# solar_collector_controller_V1_21.net
KiCad netlist of a schematic drawn in EAGLE
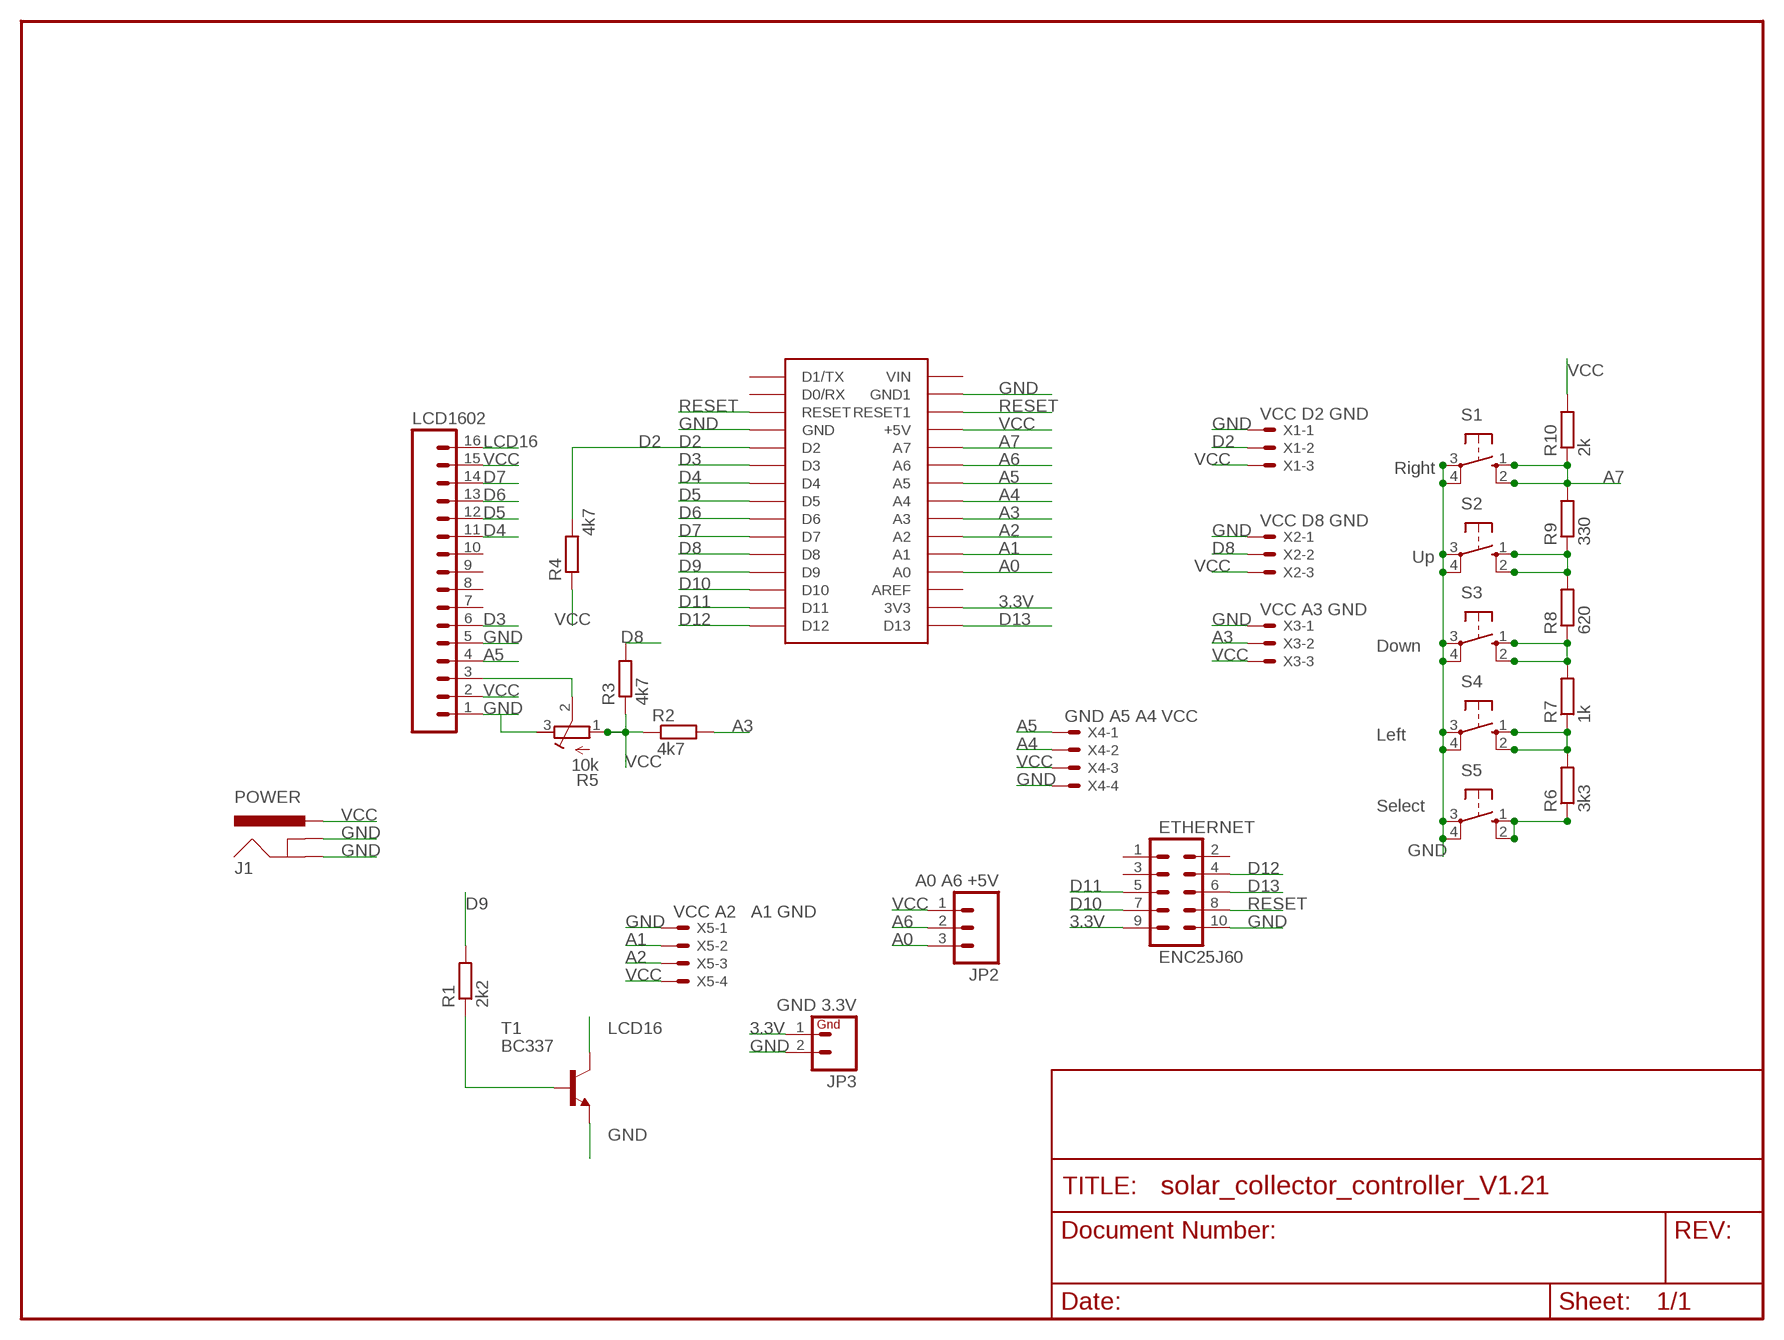
[diagram p0: schematic, sheet 1]

(export (version "E")
  (design (tool "Eeschema 10.0.6"))
  (components
    (comp (ref "ETHERNET")
      (value "ENC25J60")
      (footprint "eagle-import:AVR_ICSP")
      (libsource (lib "eagle-import") (part "M05X2PTH"))
    )
    (comp (ref "J1")
      (value "POWER")
      (footprint "eagle-import:POWER_JACK_PTH_LOCK")
      (libsource (lib "eagle-import") (part "POWER_JACKPTH_LOCK"))
    )
    (comp (ref "JP2")
      (value "A0 A6 +5V")
      (footprint "eagle-import:1X03")
      (libsource (lib "eagle-import") (part "M03PTH"))
    )
    (comp (ref "JP3")
      (value "GND 3.3V")
      (footprint "eagle-import:1X02")
      (libsource (lib "eagle-import") (part "M02PTH"))
    )
    (comp (ref "LCD1602")
      (value "HEADER-16P-2.54")
      (footprint "eagle-import:16P-2.54")
      (libsource (lib "eagle-import") (part "HEADER-16P-2.54"))
    )
    (comp (ref "R1")
      (value "2k2")
      (footprint "eagle-import:0207_10")
      (libsource (lib "eagle-import") (part "R-EU_0207/10"))
    )
    (comp (ref "R2")
      (value "4k7")
      (footprint "eagle-import:0207_10")
      (libsource (lib "eagle-import") (part "R-EU_0207/10"))
    )
    (comp (ref "R3")
      (value "4k7")
      (footprint "eagle-import:0207_10")
      (libsource (lib "eagle-import") (part "R-EU_0207/10"))
    )
    (comp (ref "R4")
      (value "4k7")
      (footprint "eagle-import:0207_10")
      (libsource (lib "eagle-import") (part "R-EU_0207/10"))
    )
    (comp (ref "R5")
      (value "10k")
      (footprint "eagle-import:RTRIM64W")
      (libsource (lib "eagle-import") (part "R-TRIMM64W"))
    )
    (comp (ref "R6")
      (value "3k3")
      (footprint "eagle-import:0207_10")
      (libsource (lib "eagle-import") (part "R-EU_0207/10"))
    )
    (comp (ref "R7")
      (value "1k")
      (footprint "eagle-import:0207_10")
      (libsource (lib "eagle-import") (part "R-EU_0207/10"))
    )
    (comp (ref "R8")
      (value "620")
      (footprint "eagle-import:0207_10")
      (libsource (lib "eagle-import") (part "R-EU_0207/10"))
    )
    (comp (ref "R9")
      (value "330")
      (footprint "eagle-import:0207_10")
      (libsource (lib "eagle-import") (part "R-EU_0207/10"))
    )
    (comp (ref "R10")
      (value "2k")
      (footprint "eagle-import:0207_10")
      (libsource (lib "eagle-import") (part "R-EU_0207/10"))
    )
    (comp (ref "S1")
      (value "Right")
      (footprint "eagle-import:B3F-10XX")
      (fields (field (name "MPN") "B3F-1000"))
      (libsource (lib "eagle-import") (part "10-XX"))
    )
    (comp (ref "S2")
      (value "Up")
      (footprint "eagle-import:B3F-10XX")
      (fields (field (name "MPN") "B3F-1000"))
      (libsource (lib "eagle-import") (part "10-XX"))
    )
    (comp (ref "S3")
      (value "Down")
      (footprint "eagle-import:B3F-10XX")
      (fields (field (name "MPN") "B3F-1000"))
      (libsource (lib "eagle-import") (part "10-XX"))
    )
    (comp (ref "S4")
      (value "Left")
      (footprint "eagle-import:B3F-10XX")
      (fields (field (name "MPN") "B3F-1000"))
      (libsource (lib "eagle-import") (part "10-XX"))
    )
    (comp (ref "S5")
      (value "Select")
      (footprint "eagle-import:B3F-10XX")
      (fields (field (name "MPN") "B3F-1000"))
      (libsource (lib "eagle-import") (part "10-XX"))
    )
    (comp (ref "T1")
      (value "BC337")
      (footprint "eagle-import:TO92")
      (libsource (lib "eagle-import") (part "BC337"))
    )
    (comp (ref "U$2")
      (value "ARDUINONANO")
      (footprint "eagle-import:PDIP-32")
      (libsource (lib "eagle-import") (part "ARDUINONANO"))
    )
    (comp (ref "X1")
      (value "VCC D2 GND")
      (footprint "eagle-import:22-23-2031")
      (fields (field (name "MF") "MOLEX") (field (name "MPN") "22-23-2031"))
      (libsource (lib "eagle-import") (part "22-23-2031"))
    )
    (comp (ref "X2")
      (value "VCC D8 GND")
      (footprint "eagle-import:22-23-2031")
      (fields (field (name "MF") "MOLEX") (field (name "MPN") "22-23-2031"))
      (libsource (lib "eagle-import") (part "22-23-2031"))
    )
    (comp (ref "X3")
      (value "VCC A3 GND")
      (footprint "eagle-import:22-23-2031")
      (fields (field (name "MF") "MOLEX") (field (name "MPN") "22-23-2031"))
      (libsource (lib "eagle-import") (part "22-23-2031"))
    )
    (comp (ref "X4")
      (value "GND A5 A4 VCC")
      (footprint "eagle-import:22-23-2041")
      (fields (field (name "MF") "MOLEX") (field (name "MPN") "22-23-2041"))
      (libsource (lib "eagle-import") (part "22-23-2041"))
    )
    (comp (ref "X5")
      (value "VCC A2 A1 GND")
      (footprint "eagle-import:22-23-2041")
      (fields (field (name "MF") "MOLEX") (field (name "MPN") "22-23-2041"))
      (libsource (lib "eagle-import") (part "22-23-2041"))
    )
  )
  (nets
    (net (code "1") (name "/3.3V") (class "Default")
      (node (ref "ETHERNET") (pin "9") (pinfunction "9_9") (pintype "passive"))
      (node (ref "JP3") (pin "1") (pinfunction "1_1") (pintype "passive"))
      (node (ref "U$2") (pin "3V3") (pinfunction "3V3_3V3") (pintype "bidirectional"))
    )
    (net (code "2") (name "/A0") (class "Default")
      (node (ref "JP2") (pin "3") (pinfunction "3_3") (pintype "passive"))
      (node (ref "U$2") (pin "A0") (pinfunction "A0_A0") (pintype "bidirectional"))
    )
    (net (code "3") (name "/A1") (class "Default")
      (node (ref "U$2") (pin "A1") (pinfunction "A1_A1") (pintype "bidirectional"))
      (node (ref "X5") (pin "2") (pinfunction "S_2") (pintype "passive"))
    )
    (net (code "4") (name "/A2") (class "Default")
      (node (ref "U$2") (pin "A2") (pinfunction "A2_A2") (pintype "bidirectional"))
      (node (ref "X5") (pin "3") (pinfunction "S_3") (pintype "passive"))
    )
    (net (code "5") (name "/A3") (class "Default")
      (node (ref "R2") (pin "2") (pinfunction "2_2") (pintype "passive"))
      (node (ref "U$2") (pin "A3") (pinfunction "A3_A3") (pintype "bidirectional"))
      (node (ref "X3") (pin "2") (pinfunction "S_2") (pintype "passive"))
    )
    (net (code "6") (name "/A4") (class "Default")
      (node (ref "U$2") (pin "A4") (pinfunction "A4_A4") (pintype "bidirectional"))
      (node (ref "X4") (pin "2") (pinfunction "S_2") (pintype "passive"))
    )
    (net (code "7") (name "/A5") (class "Default")
      (node (ref "LCD1602") (pin "4") (pinfunction "4_4") (pintype "passive"))
      (node (ref "U$2") (pin "A5") (pinfunction "A5_A5") (pintype "bidirectional"))
      (node (ref "X4") (pin "1") (pinfunction "S_1") (pintype "passive"))
    )
    (net (code "8") (name "/A6") (class "Default")
      (node (ref "JP2") (pin "2") (pinfunction "2_2") (pintype "passive"))
      (node (ref "U$2") (pin "A6") (pinfunction "A6_A6") (pintype "bidirectional"))
    )
    (net (code "9") (name "/A7") (class "Default")
      (node (ref "R10") (pin "1") (pinfunction "1_1") (pintype "passive"))
      (node (ref "R9") (pin "2") (pinfunction "2_2") (pintype "passive"))
      (node (ref "S1") (pin "1") (pinfunction "S_1") (pintype "passive"))
      (node (ref "S1") (pin "2") (pinfunction "S1_2") (pintype "passive"))
      (node (ref "U$2") (pin "A7") (pinfunction "A7_A7") (pintype "bidirectional"))
    )
    (net (code "10") (name "/D2") (class "Default")
      (node (ref "R4") (pin "2") (pinfunction "2_2") (pintype "passive"))
      (node (ref "U$2") (pin "D2") (pinfunction "D2_D2") (pintype "bidirectional"))
      (node (ref "X1") (pin "2") (pinfunction "S_2") (pintype "passive"))
    )
    (net (code "11") (name "/D3") (class "Default")
      (node (ref "LCD1602") (pin "6") (pinfunction "6_6") (pintype "passive"))
      (node (ref "U$2") (pin "D3") (pinfunction "D3_D3") (pintype "bidirectional"))
    )
    (net (code "12") (name "/D4") (class "Default")
      (node (ref "LCD1602") (pin "11") (pinfunction "11_11") (pintype "passive"))
      (node (ref "U$2") (pin "D4") (pinfunction "D4_D4") (pintype "bidirectional"))
    )
    (net (code "13") (name "/D5") (class "Default")
      (node (ref "LCD1602") (pin "12") (pinfunction "12_12") (pintype "passive"))
      (node (ref "U$2") (pin "D5") (pinfunction "D5_D5") (pintype "bidirectional"))
    )
    (net (code "14") (name "/D6") (class "Default")
      (node (ref "LCD1602") (pin "13") (pinfunction "13_13") (pintype "passive"))
      (node (ref "U$2") (pin "D6") (pinfunction "D6_D6") (pintype "bidirectional"))
    )
    (net (code "15") (name "/D7") (class "Default")
      (node (ref "LCD1602") (pin "14") (pinfunction "14_14") (pintype "passive"))
      (node (ref "U$2") (pin "D7") (pinfunction "D7_D7") (pintype "bidirectional"))
    )
    (net (code "16") (name "/D8") (class "Default")
      (node (ref "R3") (pin "2") (pinfunction "2_2") (pintype "passive"))
      (node (ref "U$2") (pin "D8") (pinfunction "D8_D8") (pintype "bidirectional"))
      (node (ref "X2") (pin "2") (pinfunction "S_2") (pintype "passive"))
    )
    (net (code "17") (name "/D9") (class "Default")
      (node (ref "R1") (pin "2") (pinfunction "2_2") (pintype "passive"))
      (node (ref "U$2") (pin "D9") (pinfunction "D9_D9") (pintype "bidirectional"))
    )
    (net (code "18") (name "/D10") (class "Default")
      (node (ref "ETHERNET") (pin "7") (pinfunction "7_7") (pintype "passive"))
      (node (ref "U$2") (pin "D10") (pinfunction "D10_D10") (pintype "bidirectional"))
    )
    (net (code "19") (name "/D11") (class "Default")
      (node (ref "ETHERNET") (pin "5") (pinfunction "5_5") (pintype "passive"))
      (node (ref "U$2") (pin "D11") (pinfunction "D11_D11") (pintype "bidirectional"))
    )
    (net (code "20") (name "/D12") (class "Default")
      (node (ref "ETHERNET") (pin "4") (pinfunction "4_4") (pintype "passive"))
      (node (ref "U$2") (pin "D12") (pinfunction "D12_D12") (pintype "bidirectional"))
    )
    (net (code "21") (name "/D13") (class "Default")
      (node (ref "ETHERNET") (pin "6") (pinfunction "6_6") (pintype "passive"))
      (node (ref "U$2") (pin "D13") (pinfunction "D13_D13") (pintype "bidirectional"))
    )
    (net (code "22") (name "/GND") (class "Default")
      (node (ref "ETHERNET") (pin "10") (pinfunction "10_10") (pintype "passive"))
      (node (ref "J1") (pin "GND") (pinfunction "GND_GND") (pintype "bidirectional"))
      (node (ref "J1") (pin "GNDBREAK") (pinfunction "GNDBREAK_GNDBREAK") (pintype "bidirectional"))
      (node (ref "JP3") (pin "2") (pinfunction "2_2") (pintype "passive"))
      (node (ref "LCD1602") (pin "1") (pinfunction "1_1") (pintype "passive"))
      (node (ref "LCD1602") (pin "5") (pinfunction "5_5") (pintype "passive"))
      (node (ref "R5") (pin "3") (pinfunction "A_3") (pintype "passive"))
      (node (ref "S1") (pin "3") (pinfunction "P_3") (pintype "passive"))
      (node (ref "S1") (pin "4") (pinfunction "P1_4") (pintype "passive"))
      (node (ref "S2") (pin "3") (pinfunction "P_3") (pintype "passive"))
      (node (ref "S2") (pin "4") (pinfunction "P1_4") (pintype "passive"))
      (node (ref "S3") (pin "3") (pinfunction "P_3") (pintype "passive"))
      (node (ref "S3") (pin "4") (pinfunction "P1_4") (pintype "passive"))
      (node (ref "S4") (pin "3") (pinfunction "P_3") (pintype "passive"))
      (node (ref "S4") (pin "4") (pinfunction "P1_4") (pintype "passive"))
      (node (ref "S5") (pin "3") (pinfunction "P_3") (pintype "passive"))
      (node (ref "S5") (pin "4") (pinfunction "P1_4") (pintype "passive"))
      (node (ref "T1") (pin "1") (pinfunction "E_1") (pintype "passive"))
      (node (ref "U$2") (pin "GND") (pinfunction "GND_GND") (pintype "bidirectional"))
      (node (ref "U$2") (pin "GND1") (pinfunction "GND1_GND1") (pintype "bidirectional"))
      (node (ref "X1") (pin "1") (pinfunction "S_1") (pintype "passive"))
      (node (ref "X2") (pin "1") (pinfunction "S_1") (pintype "passive"))
      (node (ref "X3") (pin "1") (pinfunction "S_1") (pintype "passive"))
      (node (ref "X4") (pin "4") (pinfunction "S_4") (pintype "passive"))
      (node (ref "X5") (pin "1") (pinfunction "S_1") (pintype "passive"))
    )
    (net (code "23") (name "/LCD16") (class "Default")
      (node (ref "LCD1602") (pin "16") (pinfunction "16_16") (pintype "passive"))
      (node (ref "T1") (pin "3") (pinfunction "C_3") (pintype "passive"))
    )
    (net (code "24") (name "/RESET") (class "Default")
      (node (ref "ETHERNET") (pin "8") (pinfunction "8_8") (pintype "passive"))
      (node (ref "U$2") (pin "RESET") (pinfunction "RESET_RESET") (pintype "bidirectional"))
      (node (ref "U$2") (pin "RESET1") (pinfunction "RESET1_RESET1") (pintype "bidirectional"))
    )
    (net (code "25") (name "/VCC") (class "Default")
      (node (ref "J1") (pin "PWR") (pinfunction "PWR_PWR") (pintype "bidirectional"))
      (node (ref "JP2") (pin "1") (pinfunction "1_1") (pintype "passive"))
      (node (ref "LCD1602") (pin "15") (pinfunction "15_15") (pintype "passive"))
      (node (ref "LCD1602") (pin "2") (pinfunction "2_2") (pintype "passive"))
      (node (ref "R10") (pin "2") (pinfunction "2_2") (pintype "passive"))
      (node (ref "R2") (pin "1") (pinfunction "1_1") (pintype "passive"))
      (node (ref "R3") (pin "1") (pinfunction "1_1") (pintype "passive"))
      (node (ref "R4") (pin "1") (pinfunction "1_1") (pintype "passive"))
      (node (ref "R5") (pin "1") (pinfunction "E_1") (pintype "passive"))
      (node (ref "U$2") (pin "+5V") (pinfunction "+5V_+5V") (pintype "bidirectional"))
      (node (ref "X1") (pin "3") (pinfunction "S_3") (pintype "passive"))
      (node (ref "X2") (pin "3") (pinfunction "S_3") (pintype "passive"))
      (node (ref "X3") (pin "3") (pinfunction "S_3") (pintype "passive"))
      (node (ref "X4") (pin "3") (pinfunction "S_3") (pintype "passive"))
      (node (ref "X5") (pin "4") (pinfunction "S_4") (pintype "passive"))
    )
    (net (code "26") (name "Net-(R5-S)") (class "Default")
      (node (ref "LCD1602") (pin "3") (pinfunction "3_3") (pintype "passive"))
      (node (ref "R5") (pin "2") (pinfunction "S_2") (pintype "passive"))
    )
    (net (code "27") (name "Net-(S2-S)") (class "Default")
      (node (ref "R8") (pin "2") (pinfunction "2_2") (pintype "passive"))
      (node (ref "R9") (pin "1") (pinfunction "1_1") (pintype "passive"))
      (node (ref "S2") (pin "1") (pinfunction "S_1") (pintype "passive"))
      (node (ref "S2") (pin "2") (pinfunction "S1_2") (pintype "passive"))
    )
    (net (code "28") (name "Net-(S3-S)") (class "Default")
      (node (ref "R7") (pin "2") (pinfunction "2_2") (pintype "passive"))
      (node (ref "R8") (pin "1") (pinfunction "1_1") (pintype "passive"))
      (node (ref "S3") (pin "1") (pinfunction "S_1") (pintype "passive"))
      (node (ref "S3") (pin "2") (pinfunction "S1_2") (pintype "passive"))
    )
    (net (code "29") (name "Net-(S4-S)") (class "Default")
      (node (ref "R6") (pin "2") (pinfunction "2_2") (pintype "passive"))
      (node (ref "R7") (pin "1") (pinfunction "1_1") (pintype "passive"))
      (node (ref "S4") (pin "1") (pinfunction "S_1") (pintype "passive"))
      (node (ref "S4") (pin "2") (pinfunction "S1_2") (pintype "passive"))
    )
    (net (code "30") (name "Net-(S5-S)") (class "Default")
      (node (ref "R6") (pin "1") (pinfunction "1_1") (pintype "passive"))
      (node (ref "S5") (pin "1") (pinfunction "S_1") (pintype "passive"))
      (node (ref "S5") (pin "2") (pinfunction "S1_2") (pintype "passive"))
    )
    (net (code "31") (name "Net-(T1-B)") (class "Default")
      (node (ref "R1") (pin "1") (pinfunction "1_1") (pintype "passive"))
      (node (ref "T1") (pin "2") (pinfunction "B_2") (pintype "passive"))
    )
    (net (code "32") (name "unconnected-(ETHERNET-Pad1)") (class "Default")
      (node (ref "ETHERNET") (pin "1") (pinfunction "1_1") (pintype "passive"))
    )
    (net (code "33") (name "unconnected-(ETHERNET-Pad2)") (class "Default")
      (node (ref "ETHERNET") (pin "2") (pinfunction "2_2") (pintype "passive"))
    )
    (net (code "34") (name "unconnected-(ETHERNET-Pad3)") (class "Default")
      (node (ref "ETHERNET") (pin "3") (pinfunction "3_3") (pintype "passive"))
    )
    (net (code "35") (name "unconnected-(LCD1602-Pad7)") (class "Default")
      (node (ref "LCD1602") (pin "7") (pinfunction "7_7") (pintype "passive"))
    )
    (net (code "36") (name "unconnected-(LCD1602-Pad8)") (class "Default")
      (node (ref "LCD1602") (pin "8") (pinfunction "8_8") (pintype "passive"))
    )
    (net (code "37") (name "unconnected-(LCD1602-Pad9)") (class "Default")
      (node (ref "LCD1602") (pin "9") (pinfunction "9_9") (pintype "passive"))
    )
    (net (code "38") (name "unconnected-(LCD1602-Pad10)") (class "Default")
      (node (ref "LCD1602") (pin "10") (pinfunction "10_10") (pintype "passive"))
    )
    (net (code "39") (name "unconnected-(U$2-PadAREF)") (class "Default")
      (node (ref "U$2") (pin "AREF") (pinfunction "AREF_AREF") (pintype "bidirectional"))
    )
    (net (code "40") (name "unconnected-(U$2-PadD0{slash}RX)") (class "Default")
      (node (ref "U$2") (pin "D0/RX") (pinfunction "D0/RX_D0/RX") (pintype "bidirectional"))
    )
    (net (code "41") (name "unconnected-(U$2-PadD1{slash}TX)") (class "Default")
      (node (ref "U$2") (pin "D1/TX") (pinfunction "D1/TX_D1/TX") (pintype "bidirectional"))
    )
    (net (code "42") (name "unconnected-(U$2-PadVIN)") (class "Default")
      (node (ref "U$2") (pin "VIN") (pinfunction "VIN_VIN") (pintype "bidirectional"))
    )
  )
)
